# Layer3.net
KiCad netlist of a schematic drawn in EAGLE
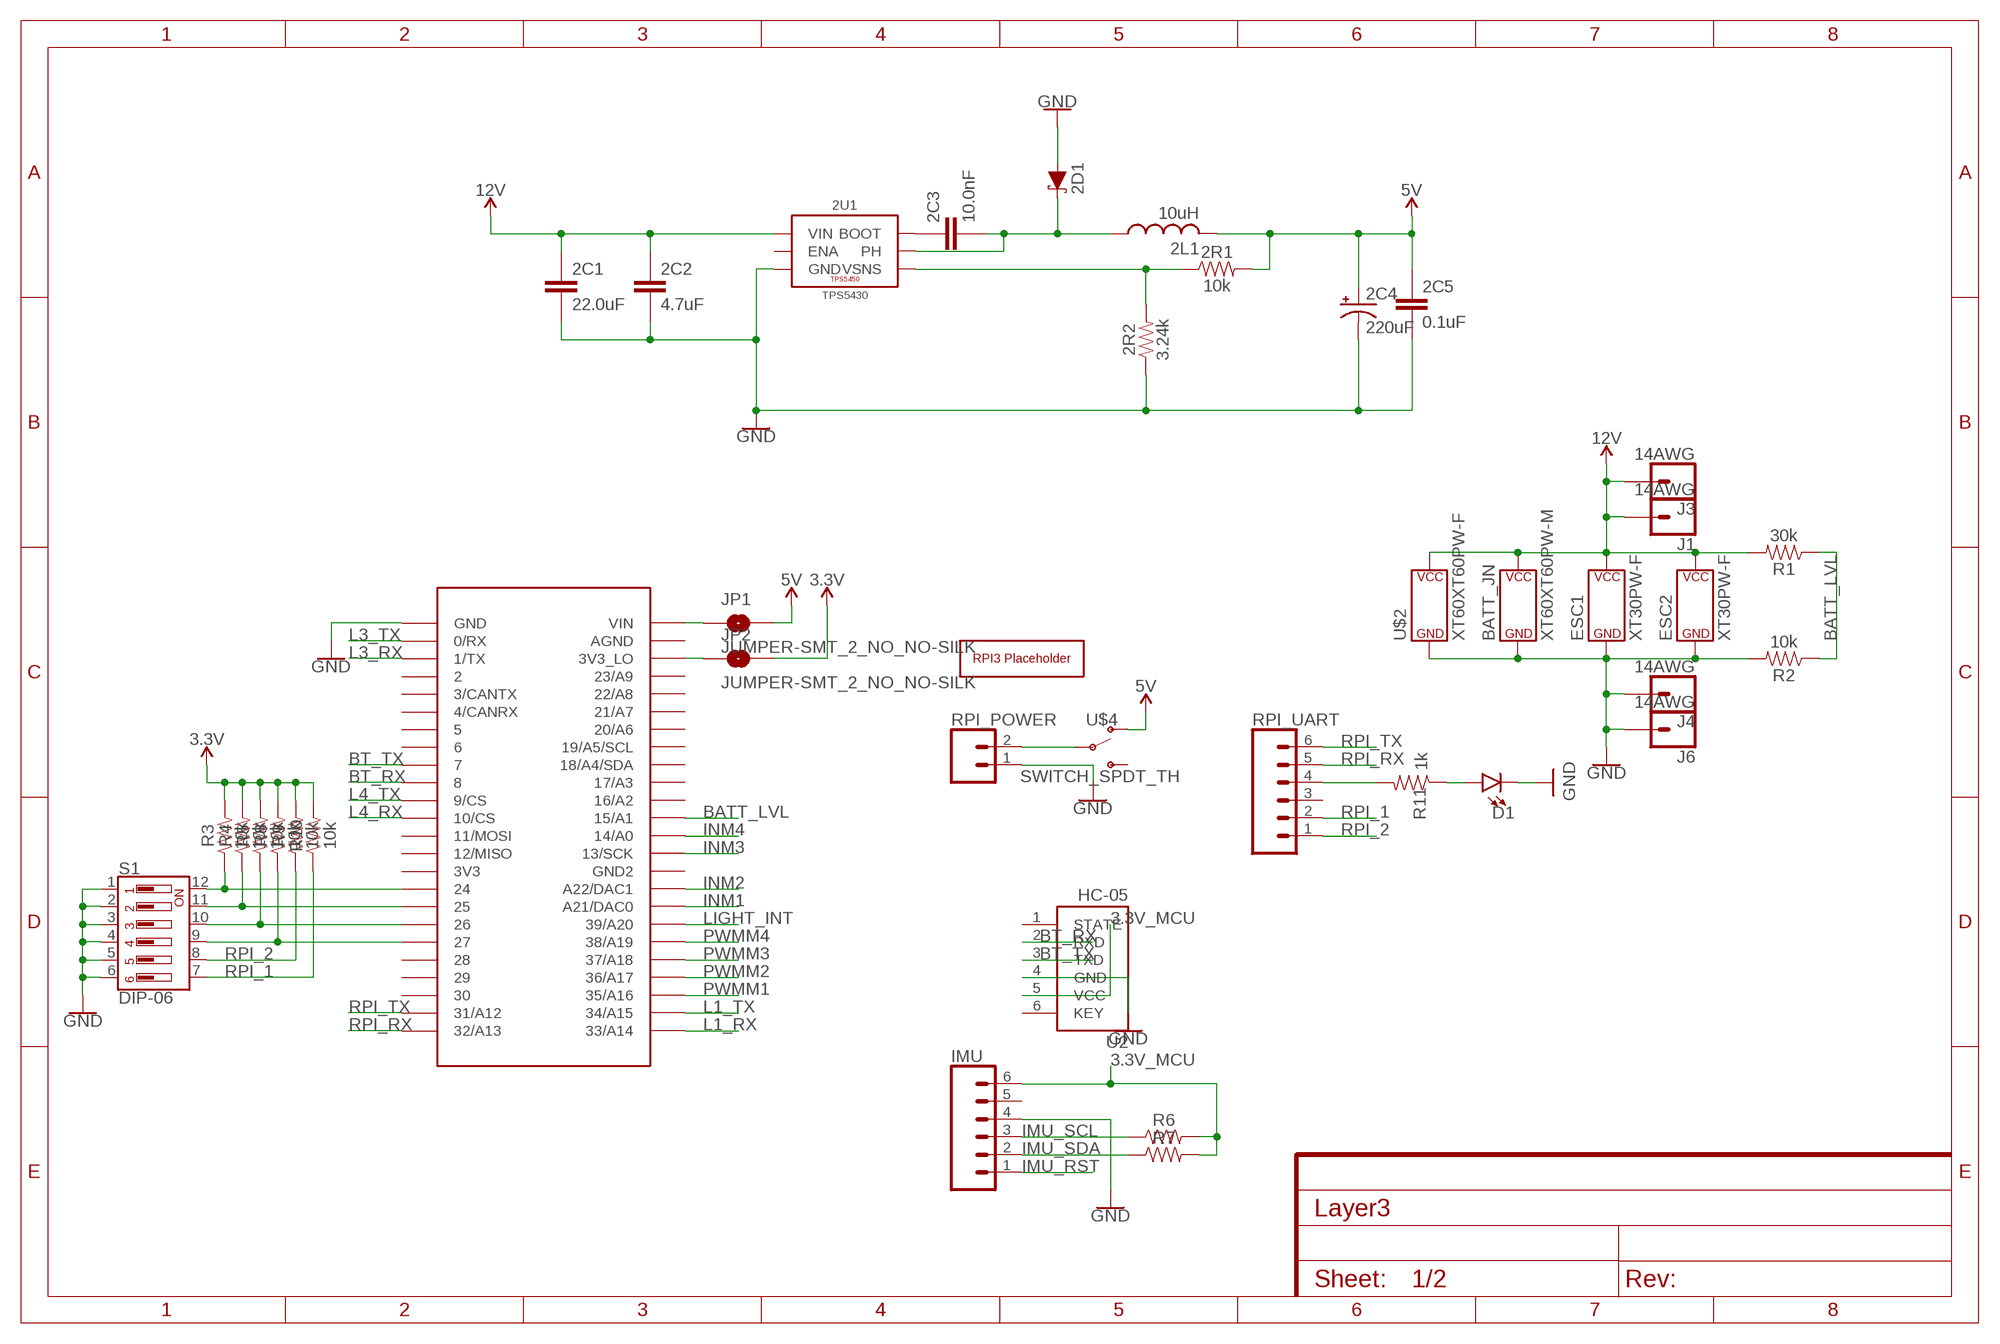
[diagram p0: schematic, sheet 1]
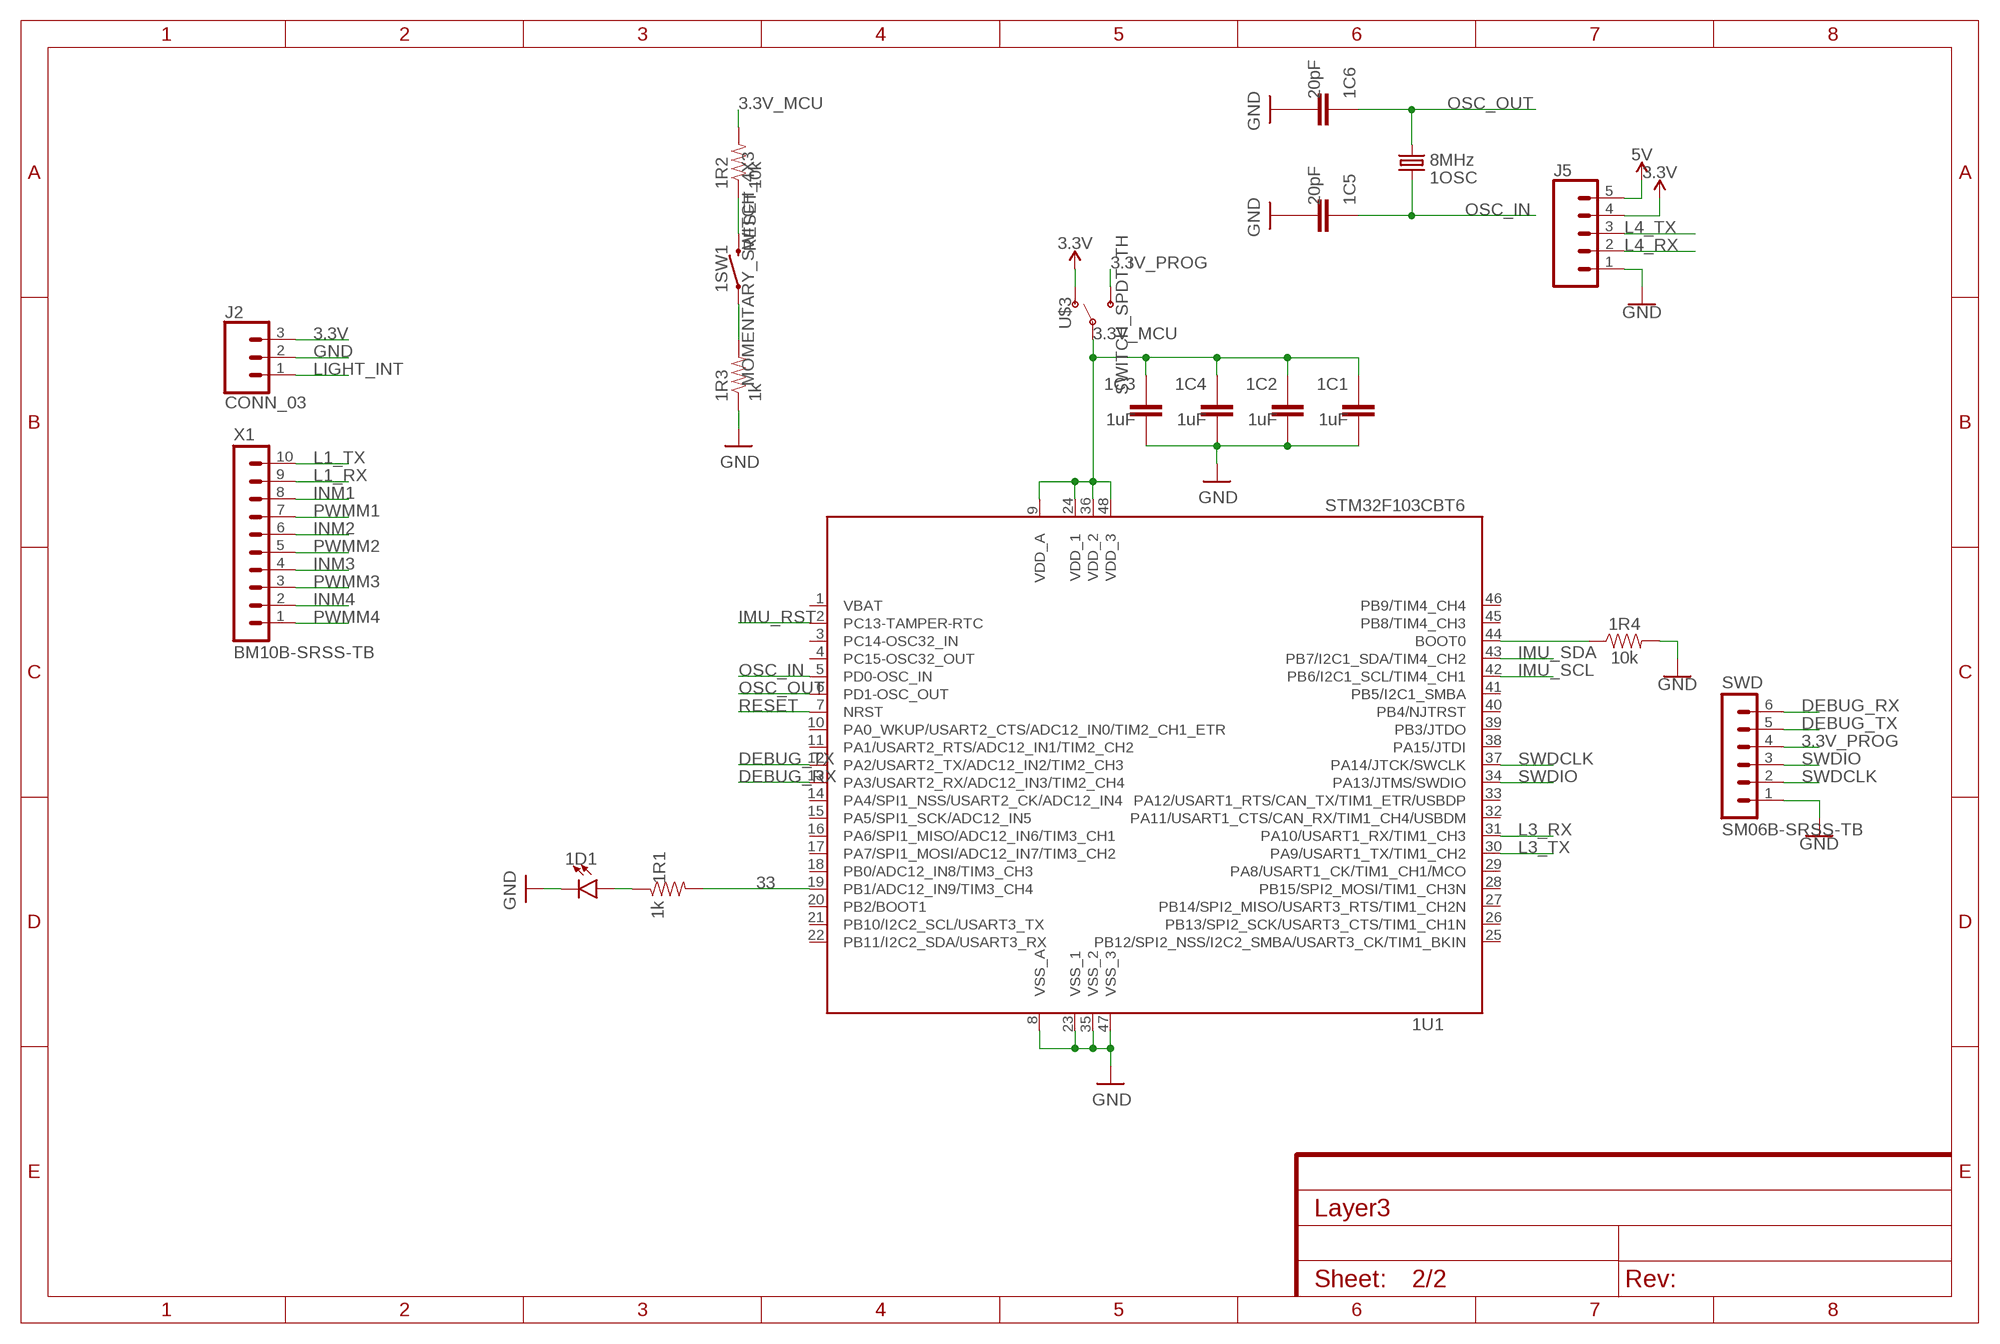
[diagram p1: schematic, sheet 2]

(export (version "E")
  (design (tool "Eeschema 10.0.6"))
  (components
    (comp (ref "1C1")
      (value "1uF")
      (footprint "eagle-import:C0603")
      (libsource (lib "eagle-import") (part "CAPACITOR0603"))
    )
    (comp (ref "1C2")
      (value "1uF")
      (footprint "eagle-import:C0603")
      (libsource (lib "eagle-import") (part "CAPACITOR0603"))
    )
    (comp (ref "1C3")
      (value "1uF")
      (footprint "eagle-import:C0603")
      (libsource (lib "eagle-import") (part "CAPACITOR0603"))
    )
    (comp (ref "1C4")
      (value "1uF")
      (footprint "eagle-import:C0603")
      (libsource (lib "eagle-import") (part "CAPACITOR0603"))
    )
    (comp (ref "1C5")
      (value "20pF")
      (footprint "eagle-import:C0603")
      (libsource (lib "eagle-import") (part "CAPACITOR0603"))
    )
    (comp (ref "1C6")
      (value "20pF")
      (footprint "eagle-import:C0603")
      (libsource (lib "eagle-import") (part "CAPACITOR0603"))
    )
    (comp (ref "1D1")
      (value "BLUE")
      (footprint "eagle-import:LED-0603")
      (libsource (lib "eagle-import") (part "LED0603"))
    )
    (comp (ref "1OSC")
      (value "8MHz")
      (footprint "eagle-import:CRYSTAL-SMD-5X3.2-2PAD")
      (libsource (lib "eagle-import") (part "CRYSTAL_5032"))
    )
    (comp (ref "1R1")
      (value "1k")
      (footprint "eagle-import:R0603")
      (libsource (lib "eagle-import") (part "RESISTOR0603"))
    )
    (comp (ref "1R2")
      (value "10k")
      (footprint "eagle-import:R0603")
      (libsource (lib "eagle-import") (part "RESISTOR0603"))
    )
    (comp (ref "1R3")
      (value "1k")
      (footprint "eagle-import:R0603")
      (libsource (lib "eagle-import") (part "RESISTOR0603"))
    )
    (comp (ref "1R4")
      (value "10k")
      (footprint "eagle-import:R0603")
      (libsource (lib "eagle-import") (part "RESISTOR0603"))
    )
    (comp (ref "1SW1")
      (value "MOMENTARY_SWITCH_4X3")
      (footprint "eagle-import:MOMENTARY_SWITCH_4X3")
      (libsource (lib "eagle-import") (part "MOMENTARY_SWITCH_4X3"))
    )
    (comp (ref "1U1")
      (value "STM32F103CBT6")
      (footprint "eagle-import:LQFP48")
      (libsource (lib "eagle-import") (part "STM32F103CBT6"))
    )
    (comp (ref "J2")
      (value "CONN_03")
      (footprint "eagle-import:1X03_LOCK")
      (libsource (lib "eagle-import") (part "CONN_03"))
    )
    (comp (ref "J5")
      (value "CONN_05LOCK")
      (footprint "eagle-import:1X05_LOCK")
      (libsource (lib "eagle-import") (part "CONN_05LOCK"))
    )
    (comp (ref "SWD")
      (value "SM06B-SRSS-TB")
      (footprint "eagle-import:SM06B-SRSS-TB")
      (libsource (lib "eagle-import") (part "SM06B-SRSS-TB"))
    )
    (comp (ref "U$3")
      (value "SWITCH_SPDT_TH")
      (footprint "eagle-import:SWITCH_SPDT_PTH_11.6X4.0MM_LOCK")
      (libsource (lib "eagle-import") (part "SWITCH_SPDT_TH"))
    )
    (comp (ref "X1")
      (value "BM10B-SRSS-TB")
      (footprint "eagle-import:BM10B-SRSS-TB")
      (libsource (lib "eagle-import") (part "BM10B-SRSS-TB"))
    )
    (comp (ref "2C1")
      (value "22.0uF")
      (footprint "eagle-import:C1210")
      (libsource (lib "eagle-import") (part "CAPACITOR1210"))
    )
    (comp (ref "2C2")
      (value "4.7uF")
      (footprint "eagle-import:C0603")
      (libsource (lib "eagle-import") (part "CAPACITOR0603"))
    )
    (comp (ref "2C3")
      (value "10.0nF")
      (footprint "eagle-import:C0603")
      (libsource (lib "eagle-import") (part "CAPACITOR0603"))
    )
    (comp (ref "2C4")
      (value "220uF")
      (footprint "eagle-import:D_7343-31R")
      (libsource (lib "eagle-import") (part "CPOL-USD/7343-31R"))
    )
    (comp (ref "2C5")
      (value "0.1uF")
      (footprint "eagle-import:C0603")
      (libsource (lib "eagle-import") (part "CAPACITOR0603"))
    )
    (comp (ref "2D1")
      (value "3A/40V/500mV")
      (footprint "eagle-import:SMA-DIODE")
      (libsource (lib "eagle-import") (part "DIODE-SCHOTTKY"))
    )
    (comp (ref "2L1")
      (value "10uH")
      (footprint "eagle-import:SWPA8040")
      (libsource (lib "eagle-import") (part "INDUCTORSWPA8040"))
    )
    (comp (ref "2R1")
      (value "10k")
      (footprint "eagle-import:R0603")
      (libsource (lib "eagle-import") (part "RESISTOR0603"))
    )
    (comp (ref "2R2")
      (value "3.24k")
      (footprint "eagle-import:R0603")
      (libsource (lib "eagle-import") (part "RESISTOR0603"))
    )
    (comp (ref "2U1")
      (value "TPS5430")
      (footprint "eagle-import:POWERPAD-SOIC-8")
      (libsource (lib "eagle-import") (part "TPS5450"))
    )
    (comp (ref "BATT_JN")
      (value "XT60XT60PW-M")
      (footprint "eagle-import:XT60PW-M")
      (libsource (lib "eagle-import") (part "XT60XT60PW-M"))
    )
    (comp (ref "D1")
      (value "BLUE")
      (footprint "eagle-import:LED-0603")
      (libsource (lib "eagle-import") (part "LED0603"))
    )
    (comp (ref "ESC1")
      (value "XT30PW-F")
      (footprint "eagle-import:XT30PW-F")
      (libsource (lib "eagle-import") (part "XT30PW-F"))
    )
    (comp (ref "ESC2")
      (value "XT30PW-F")
      (footprint "eagle-import:XT30PW-F")
      (libsource (lib "eagle-import") (part "XT30PW-F"))
    )
    (comp (ref "IMU")
      (value "CONN_06FEMALE_LOCK")
      (footprint "eagle-import:1X06_FEMALE_LOCK.010")
      (libsource (lib "eagle-import") (part "SparkFun-Connectors_513_CONN_06FEMALE_LOCK"))
    )
    (comp (ref "J1")
      (value "14AWG")
      (footprint "eagle-import:14AWG")
      (libsource (lib "eagle-import") (part "14AWG"))
    )
    (comp (ref "J3")
      (value "14AWG")
      (footprint "eagle-import:14AWG")
      (libsource (lib "eagle-import") (part "14AWG"))
    )
    (comp (ref "J4")
      (value "14AWG")
      (footprint "eagle-import:14AWG")
      (libsource (lib "eagle-import") (part "14AWG"))
    )
    (comp (ref "J6")
      (value "14AWG")
      (footprint "eagle-import:14AWG")
      (libsource (lib "eagle-import") (part "14AWG"))
    )
    (comp (ref "JP1")
      (value "JUMPER-SMT_2_NO_NO-SILK")
      (footprint "eagle-import:SMT-JUMPER_2_NO_NO-SILK")
      (libsource (lib "eagle-import") (part "JUMPER-SMT_2_NO_NO-SILK"))
    )
    (comp (ref "JP2")
      (value "JUMPER-SMT_2_NO_NO-SILK")
      (footprint "eagle-import:SMT-JUMPER_2_NO_NO-SILK")
      (libsource (lib "eagle-import") (part "JUMPER-SMT_2_NO_NO-SILK"))
    )
    (comp (ref "PCB1")
      (value "RPI3")
      (footprint "eagle-import:RPI3")
      (libsource (lib "eagle-import") (part "RPI3"))
    )
    (comp (ref "R1")
      (value "30k")
      (footprint "eagle-import:R0603")
      (libsource (lib "eagle-import") (part "RESISTOR0603"))
    )
    (comp (ref "R2")
      (value "10k")
      (footprint "eagle-import:R0603")
      (libsource (lib "eagle-import") (part "RESISTOR0603"))
    )
    (comp (ref "R3")
      (value "10k")
      (footprint "eagle-import:R0603")
      (libsource (lib "eagle-import") (part "RESISTOR0603"))
    )
    (comp (ref "R4")
      (value "10k")
      (footprint "eagle-import:R0603")
      (libsource (lib "eagle-import") (part "RESISTOR0603"))
    )
    (comp (ref "R5")
      (value "10k")
      (footprint "eagle-import:R0603")
      (libsource (lib "eagle-import") (part "RESISTOR0603"))
    )
    (comp (ref "R6")
      (value "RESISTOR0603")
      (footprint "eagle-import:R0603")
      (libsource (lib "eagle-import") (part "RESISTOR0603"))
    )
    (comp (ref "R7")
      (value "RESISTOR0603")
      (footprint "eagle-import:R0603")
      (libsource (lib "eagle-import") (part "RESISTOR0603"))
    )
    (comp (ref "R8")
      (value "10k")
      (footprint "eagle-import:R0603")
      (libsource (lib "eagle-import") (part "RESISTOR0603"))
    )
    (comp (ref "R9")
      (value "10k")
      (footprint "eagle-import:R0603")
      (libsource (lib "eagle-import") (part "RESISTOR0603"))
    )
    (comp (ref "R10")
      (value "10k")
      (footprint "eagle-import:R0603")
      (libsource (lib "eagle-import") (part "RESISTOR0603"))
    )
    (comp (ref "R11")
      (value "1k")
      (footprint "eagle-import:R0603")
      (libsource (lib "eagle-import") (part "RESISTOR0603"))
    )
    (comp (ref "RPI_POWER")
      (value "CONN_02LOCK")
      (footprint "eagle-import:1X02_LOCK")
      (libsource (lib "eagle-import") (part "CONN_02LOCK"))
    )
    (comp (ref "RPI_UART")
      (value "CONN_06LOCK")
      (footprint "eagle-import:1X06_LOCK")
      (libsource (lib "eagle-import") (part "CONN_06LOCK"))
    )
    (comp (ref "S1")
      (value "DIP-06")
      (footprint "eagle-import:DIPSWITCH-06-SMD")
      (libsource (lib "eagle-import") (part "DIP-06"))
    )
    (comp (ref "U$1")
      (value "TEENSY_3.5/3.6_NO_MIDDLE")
      (footprint "eagle-import:TEENSY_3.5_3.6_NO_MIDDLE")
      (libsource (lib "eagle-import") (part "TEENSY_3.5/3.6_NO_MIDDLE"))
    )
    (comp (ref "U$2")
      (value "XT60XT60PW-F")
      (footprint "eagle-import:XT60PW-F")
      (libsource (lib "eagle-import") (part "XT60XT60PW-F"))
    )
    (comp (ref "U$4")
      (value "SWITCH_SPDT_TH")
      (footprint "eagle-import:SWITCH_SPDT_PTH_11.6X4.0MM_LOCK")
      (libsource (lib "eagle-import") (part "SWITCH_SPDT_TH"))
    )
    (comp (ref "U2")
      (value "HC-05_BENT")
      (footprint "eagle-import:HC-05_BENT")
      (libsource (lib "eagle-import") (part "HC-05_BENT"))
    )
  )
  (nets
    (net (code "1") (name "3.3V") (class "Default")
      (node (ref "J2") (pin "3") (pinfunction "3_3") (pintype "passive"))
      (node (ref "J5") (pin "4") (pinfunction "4_4") (pintype "passive"))
      (node (ref "JP2") (pin "2") (pinfunction "2_2") (pintype "passive"))
      (node (ref "R10") (pin "2") (pinfunction "2_2") (pintype "passive"))
      (node (ref "R3") (pin "2") (pinfunction "2_2") (pintype "passive"))
      (node (ref "R4") (pin "2") (pinfunction "2_2") (pintype "passive"))
      (node (ref "R5") (pin "2") (pinfunction "2_2") (pintype "passive"))
      (node (ref "R8") (pin "2") (pinfunction "2_2") (pintype "passive"))
      (node (ref "R9") (pin "2") (pinfunction "2_2") (pintype "passive"))
      (node (ref "U$3") (pin "1") (pinfunction "O_1") (pintype "passive"))
    )
    (net (code "2") (name "3.3V_MCU") (class "Default")
      (node (ref "1C1") (pin "1") (pinfunction "1_1") (pintype "passive"))
      (node (ref "1C2") (pin "1") (pinfunction "1_1") (pintype "passive"))
      (node (ref "1C3") (pin "1") (pinfunction "1_1") (pintype "passive"))
      (node (ref "1C4") (pin "1") (pinfunction "1_1") (pintype "passive"))
      (node (ref "1R2") (pin "2") (pinfunction "2_2") (pintype "passive"))
      (node (ref "1U1") (pin "24") (pinfunction "VDD_1_24") (pintype "power_in"))
      (node (ref "1U1") (pin "36") (pinfunction "VDD_2_36") (pintype "power_in"))
      (node (ref "1U1") (pin "48") (pinfunction "VDD_3_48") (pintype "power_in"))
      (node (ref "1U1") (pin "9") (pinfunction "VDD_A_9") (pintype "power_in"))
      (node (ref "IMU") (pin "6") (pinfunction "6_6") (pintype "passive"))
      (node (ref "R6") (pin "2") (pinfunction "2_2") (pintype "passive"))
      (node (ref "R7") (pin "2") (pinfunction "2_2") (pintype "passive"))
      (node (ref "U$3") (pin "2") (pinfunction "P_2") (pintype "passive"))
      (node (ref "U2") (pin "5") (pinfunction "VCC_5") (pintype "power_in"))
    )
    (net (code "3") (name "3.3V_PROG") (class "Default")
      (node (ref "SWD") (pin "4") (pinfunction "4_4") (pintype "passive"))
      (node (ref "U$3") (pin "3") (pinfunction "S_3") (pintype "passive"))
    )
    (net (code "4") (name "5V") (class "Default")
      (node (ref "2C4") (pin "+") (pinfunction "+_+") (pintype "passive"))
      (node (ref "2C5") (pin "1") (pinfunction "1_1") (pintype "passive"))
      (node (ref "2L1") (pin "P2") (pinfunction "2_P2") (pintype "passive"))
      (node (ref "2R1") (pin "2") (pinfunction "2_2") (pintype "passive"))
      (node (ref "J5") (pin "5") (pinfunction "5_5") (pintype "passive"))
      (node (ref "JP1") (pin "2") (pinfunction "2_2") (pintype "passive"))
      (node (ref "U$4") (pin "1") (pinfunction "O_1") (pintype "passive"))
    )
    (net (code "5") (name "12V") (class "Default")
      (node (ref "2C1") (pin "1") (pinfunction "1_1") (pintype "passive"))
      (node (ref "2C2") (pin "1") (pinfunction "1_1") (pintype "passive"))
      (node (ref "2U1") (pin "7") (pinfunction "VIN_7") (pintype "power_in"))
      (node (ref "BATT_JN") (pin "+") (pinfunction "P$V+_+") (pintype "bidirectional"))
      (node (ref "ESC1") (pin "+") (pinfunction "P$V+_+") (pintype "bidirectional"))
      (node (ref "ESC2") (pin "+") (pinfunction "P$V+_+") (pintype "bidirectional"))
      (node (ref "J1") (pin "P$1") (pinfunction "1_P$1") (pintype "passive"))
      (node (ref "J3") (pin "P$1") (pinfunction "1_P$1") (pintype "passive"))
      (node (ref "R1") (pin "2") (pinfunction "2_2") (pintype "passive"))
      (node (ref "U$2") (pin "+") (pinfunction "P$V+_+") (pintype "bidirectional"))
    )
    (net (code "6") (name "33") (class "Default")
      (node (ref "1R1") (pin "2") (pinfunction "2_2") (pintype "passive"))
      (node (ref "1U1") (pin "19") (pinfunction "PB1/ADC12_IN9/TIM3_CH4_19") (pintype "bidirectional"))
    )
    (net (code "7") (name "BATT_LVL") (class "Default")
      (node (ref "R1") (pin "1") (pinfunction "1_1") (pintype "passive"))
      (node (ref "R2") (pin "1") (pinfunction "1_1") (pintype "passive"))
      (node (ref "U$1") (pin "15/A1") (pinfunction "15/A1_15/A1") (pintype "bidirectional"))
    )
    (net (code "8") (name "BT_RX") (class "Default")
      (node (ref "U$1") (pin "8") (pinfunction "8_8") (pintype "bidirectional"))
      (node (ref "U2") (pin "2") (pinfunction "RXD_2") (pintype "bidirectional"))
    )
    (net (code "9") (name "BT_TX") (class "Default")
      (node (ref "U$1") (pin "7") (pinfunction "7_7") (pintype "bidirectional"))
      (node (ref "U2") (pin "3") (pinfunction "TXD_3") (pintype "bidirectional"))
    )
    (net (code "10") (name "DEBUG_RX") (class "Default")
      (node (ref "1U1") (pin "13") (pinfunction "PA3/USART2_RX/ADC12_IN3/TIM2_CH4_13") (pintype "bidirectional"))
      (node (ref "SWD") (pin "6") (pinfunction "6_6") (pintype "passive"))
    )
    (net (code "11") (name "DEBUG_TX") (class "Default")
      (node (ref "1U1") (pin "12") (pinfunction "PA2/USART2_TX/ADC12_IN2/TIM2_CH3_12") (pintype "bidirectional"))
      (node (ref "SWD") (pin "5") (pinfunction "5_5") (pintype "passive"))
    )
    (net (code "12") (name "GND") (class "Default")
      (node (ref "1C1") (pin "2") (pinfunction "2_2") (pintype "passive"))
      (node (ref "1C2") (pin "2") (pinfunction "2_2") (pintype "passive"))
      (node (ref "1C3") (pin "2") (pinfunction "2_2") (pintype "passive"))
      (node (ref "1C4") (pin "2") (pinfunction "2_2") (pintype "passive"))
      (node (ref "1C5") (pin "2") (pinfunction "2_2") (pintype "passive"))
      (node (ref "1C6") (pin "2") (pinfunction "2_2") (pintype "passive"))
      (node (ref "1D1") (pin "C") (pinfunction "C_C") (pintype "passive"))
      (node (ref "1R3") (pin "1") (pinfunction "1_1") (pintype "passive"))
      (node (ref "1R4") (pin "2") (pinfunction "2_2") (pintype "passive"))
      (node (ref "1U1") (pin "23") (pinfunction "VSS_1_23") (pintype "power_in"))
      (node (ref "1U1") (pin "35") (pinfunction "VSS_2_35") (pintype "power_in"))
      (node (ref "1U1") (pin "47") (pinfunction "VSS_3_47") (pintype "power_in"))
      (node (ref "1U1") (pin "8") (pinfunction "VSS_A_8") (pintype "power_in"))
      (node (ref "2C1") (pin "2") (pinfunction "2_2") (pintype "passive"))
      (node (ref "2C2") (pin "2") (pinfunction "2_2") (pintype "passive"))
      (node (ref "2C4") (pin "-") (pinfunction "-_-") (pintype "passive"))
      (node (ref "2C5") (pin "2") (pinfunction "2_2") (pintype "passive"))
      (node (ref "2D1") (pin "A") (pinfunction "A_A") (pintype "passive"))
      (node (ref "2R2") (pin "1") (pinfunction "1_1") (pintype "passive"))
      (node (ref "2U1") (pin "6") (pinfunction "GND_6") (pintype "power_in"))
      (node (ref "2U1") (pin "9") (pinfunction "GND_9") (pintype "power_in"))
      (node (ref "2U1") (pin "P$1") (pinfunction "GND_P$1") (pintype "power_in"))
      (node (ref "2U1") (pin "P$2") (pinfunction "GND_P$2") (pintype "power_in"))
      (node (ref "2U1") (pin "P$3") (pinfunction "GND_P$3") (pintype "power_in"))
      (node (ref "2U1") (pin "P$4") (pinfunction "GND_P$4") (pintype "power_in"))
      (node (ref "2U1") (pin "P$5") (pinfunction "GND_P$5") (pintype "power_in"))
      (node (ref "2U1") (pin "P$6") (pinfunction "GND_P$6") (pintype "power_in"))
      (node (ref "BATT_JN") (pin "-") (pinfunction "P$V-_-") (pintype "bidirectional"))
      (node (ref "D1") (pin "C") (pinfunction "C_C") (pintype "passive"))
      (node (ref "ESC1") (pin "-") (pinfunction "P$V-_-") (pintype "bidirectional"))
      (node (ref "ESC2") (pin "-") (pinfunction "P$V-_-") (pintype "bidirectional"))
      (node (ref "IMU") (pin "4") (pinfunction "4_4") (pintype "passive"))
      (node (ref "J2") (pin "2") (pinfunction "2_2") (pintype "passive"))
      (node (ref "J4") (pin "P$1") (pinfunction "1_P$1") (pintype "passive"))
      (node (ref "J5") (pin "1") (pinfunction "1_1") (pintype "passive"))
      (node (ref "J6") (pin "P$1") (pinfunction "1_P$1") (pintype "passive"))
      (node (ref "R2") (pin "2") (pinfunction "2_2") (pintype "passive"))
      (node (ref "RPI_POWER") (pin "1") (pinfunction "1_1") (pintype "passive"))
      (node (ref "S1") (pin "1") (pinfunction "1_1") (pintype "bidirectional"))
      (node (ref "S1") (pin "2") (pinfunction "2_2") (pintype "bidirectional"))
      (node (ref "S1") (pin "3") (pinfunction "3_3") (pintype "bidirectional"))
      (node (ref "S1") (pin "4") (pinfunction "4_4") (pintype "bidirectional"))
      (node (ref "S1") (pin "5") (pinfunction "5_5") (pintype "bidirectional"))
      (node (ref "S1") (pin "6") (pinfunction "6_6") (pintype "bidirectional"))
      (node (ref "SWD") (pin "1") (pinfunction "1_1") (pintype "passive"))
      (node (ref "U$1") (pin "GND") (pinfunction "GND_GND") (pintype "bidirectional"))
      (node (ref "U$2") (pin "-") (pinfunction "P$V-_-") (pintype "bidirectional"))
      (node (ref "U2") (pin "4") (pinfunction "GND_4") (pintype "power_in"))
    )
    (net (code "13") (name "IMU_RST") (class "Default")
      (node (ref "1U1") (pin "2") (pinfunction "PC13-TAMPER-RTC_2") (pintype "input"))
      (node (ref "IMU") (pin "1") (pinfunction "1_1") (pintype "passive"))
    )
    (net (code "14") (name "IMU_SCL") (class "Default")
      (node (ref "1U1") (pin "42") (pinfunction "PB6/I2C1_SCL/TIM4_CH1_42") (pintype "input"))
      (node (ref "IMU") (pin "3") (pinfunction "3_3") (pintype "passive"))
      (node (ref "R6") (pin "1") (pinfunction "1_1") (pintype "passive"))
    )
    (net (code "15") (name "IMU_SDA") (class "Default")
      (node (ref "1U1") (pin "43") (pinfunction "PB7/I2C1_SDA/TIM4_CH2_43") (pintype "bidirectional"))
      (node (ref "IMU") (pin "2") (pinfunction "2_2") (pintype "passive"))
      (node (ref "R7") (pin "1") (pinfunction "1_1") (pintype "passive"))
    )
    (net (code "16") (name "INM1") (class "Default")
      (node (ref "U$1") (pin "A21/DAC0") (pinfunction "A21/DAC0_A21/DAC0") (pintype "bidirectional"))
      (node (ref "X1") (pin "8") (pinfunction "8_8") (pintype "passive"))
    )
    (net (code "17") (name "INM2") (class "Default")
      (node (ref "U$1") (pin "A22/DAC1") (pinfunction "A22/DAC1_A22/DAC1") (pintype "bidirectional"))
      (node (ref "X1") (pin "6") (pinfunction "6_6") (pintype "passive"))
    )
    (net (code "18") (name "INM3") (class "Default")
      (node (ref "U$1") (pin "13/SCK") (pinfunction "13/SCK_13/SCK") (pintype "bidirectional"))
      (node (ref "X1") (pin "4") (pinfunction "4_4") (pintype "passive"))
    )
    (net (code "19") (name "INM4") (class "Default")
      (node (ref "U$1") (pin "14/A0") (pinfunction "14/A0_14/A0") (pintype "bidirectional"))
      (node (ref "X1") (pin "2") (pinfunction "2_2") (pintype "passive"))
    )
    (net (code "20") (name "L1_RX") (class "Default")
      (node (ref "U$1") (pin "33/A14") (pinfunction "33/A14_33/A14") (pintype "bidirectional"))
      (node (ref "X1") (pin "9") (pinfunction "9_9") (pintype "passive"))
    )
    (net (code "21") (name "L1_TX") (class "Default")
      (node (ref "U$1") (pin "34/A15") (pinfunction "34/A15_34/A15") (pintype "bidirectional"))
      (node (ref "X1") (pin "10") (pinfunction "10_10") (pintype "passive"))
    )
    (net (code "22") (name "L3_RX") (class "Default")
      (node (ref "1U1") (pin "31") (pinfunction "PA10/USART1_RX/TIM1_CH3_31") (pintype "bidirectional"))
      (node (ref "U$1") (pin "1/TX") (pinfunction "1/TX_1/TX") (pintype "bidirectional"))
    )
    (net (code "23") (name "L3_TX") (class "Default")
      (node (ref "1U1") (pin "30") (pinfunction "PA9/USART1_TX/TIM1_CH2_30") (pintype "input"))
      (node (ref "U$1") (pin "0/RX") (pinfunction "0/RX_0/RX") (pintype "bidirectional"))
    )
    (net (code "24") (name "L4_RX") (class "Default")
      (node (ref "J5") (pin "2") (pinfunction "2_2") (pintype "passive"))
      (node (ref "U$1") (pin "10/CS") (pinfunction "10/CS_10/CS") (pintype "bidirectional"))
    )
    (net (code "25") (name "L4_TX") (class "Default")
      (node (ref "J5") (pin "3") (pinfunction "3_3") (pintype "passive"))
      (node (ref "U$1") (pin "9/CS") (pinfunction "9/CS_9/CS") (pintype "bidirectional"))
    )
    (net (code "26") (name "LIGHT_INT") (class "Default")
      (node (ref "J2") (pin "1") (pinfunction "1_1") (pintype "passive"))
      (node (ref "U$1") (pin "39/A20") (pinfunction "39/A20_39/A20") (pintype "bidirectional"))
    )
    (net (code "27") (name "Net-(1D1-PadA)") (class "Default")
      (node (ref "1D1") (pin "A") (pinfunction "A_A") (pintype "passive"))
      (node (ref "1R1") (pin "1") (pinfunction "1_1") (pintype "passive"))
    )
    (net (code "28") (name "Net-(1SW1-1)") (class "Default")
      (node (ref "1R3") (pin "2") (pinfunction "2_2") (pintype "passive"))
      (node (ref "1SW1") (pin "P$1") (pinfunction "1_P$1") (pintype "passive"))
    )
    (net (code "29") (name "Net-(1U1-BOOT0)") (class "Default")
      (node (ref "1R4") (pin "1") (pinfunction "1_1") (pintype "passive"))
      (node (ref "1U1") (pin "44") (pinfunction "BOOT0_44") (pintype "input"))
    )
    (net (code "30") (name "Net-(2L1-1)") (class "Default")
      (node (ref "2C3") (pin "2") (pinfunction "2_2") (pintype "passive"))
      (node (ref "2D1") (pin "C") (pinfunction "C_C") (pintype "passive"))
      (node (ref "2L1") (pin "P1") (pinfunction "1_P1") (pintype "passive"))
      (node (ref "2U1") (pin "8") (pinfunction "PH_8") (pintype "bidirectional"))
    )
    (net (code "31") (name "Net-(2U1-BOOT)") (class "Default")
      (node (ref "2C3") (pin "1") (pinfunction "1_1") (pintype "passive"))
      (node (ref "2U1") (pin "1") (pinfunction "BOOT_1") (pintype "bidirectional"))
    )
    (net (code "32") (name "Net-(2U1-VSNS)") (class "Default")
      (node (ref "2R1") (pin "1") (pinfunction "1_1") (pintype "passive"))
      (node (ref "2R2") (pin "2") (pinfunction "2_2") (pintype "passive"))
      (node (ref "2U1") (pin "4") (pinfunction "VSNS_4") (pintype "input"))
    )
    (net (code "33") (name "Net-(D1-PadA)") (class "Default")
      (node (ref "D1") (pin "A") (pinfunction "A_A") (pintype "passive"))
      (node (ref "R11") (pin "1") (pinfunction "1_1") (pintype "passive"))
    )
    (net (code "34") (name "Net-(JP1-Pad1)") (class "Default")
      (node (ref "JP1") (pin "1") (pinfunction "1_1") (pintype "passive"))
      (node (ref "U$1") (pin "VIN") (pinfunction "VIN_VIN") (pintype "bidirectional"))
    )
    (net (code "35") (name "Net-(JP2-Pad1)") (class "Default")
      (node (ref "JP2") (pin "1") (pinfunction "1_1") (pintype "passive"))
      (node (ref "U$1") (pin "3V3_LO") (pinfunction "3V3_LO_3V3_LO") (pintype "bidirectional"))
    )
    (net (code "36") (name "Net-(R3-Pad1)") (class "Default")
      (node (ref "R3") (pin "1") (pinfunction "1_1") (pintype "passive"))
      (node (ref "S1") (pin "12") (pinfunction "12_12") (pintype "bidirectional"))
      (node (ref "U$1") (pin "24") (pinfunction "24_24") (pintype "bidirectional"))
    )
    (net (code "37") (name "Net-(R4-Pad1)") (class "Default")
      (node (ref "R4") (pin "1") (pinfunction "1_1") (pintype "passive"))
      (node (ref "S1") (pin "11") (pinfunction "11_11") (pintype "bidirectional"))
      (node (ref "U$1") (pin "25") (pinfunction "25_25") (pintype "bidirectional"))
    )
    (net (code "38") (name "Net-(R5-Pad1)") (class "Default")
      (node (ref "R5") (pin "1") (pinfunction "1_1") (pintype "passive"))
      (node (ref "S1") (pin "10") (pinfunction "10_10") (pintype "bidirectional"))
      (node (ref "U$1") (pin "26") (pinfunction "26_26") (pintype "bidirectional"))
    )
    (net (code "39") (name "Net-(R8-Pad1)") (class "Default")
      (node (ref "R8") (pin "1") (pinfunction "1_1") (pintype "passive"))
      (node (ref "S1") (pin "9") (pinfunction "9_9") (pintype "bidirectional"))
      (node (ref "U$1") (pin "27") (pinfunction "27_27") (pintype "bidirectional"))
    )
    (net (code "40") (name "Net-(R11-Pad2)") (class "Default")
      (node (ref "R11") (pin "2") (pinfunction "2_2") (pintype "passive"))
      (node (ref "RPI_UART") (pin "4") (pinfunction "4_4") (pintype "passive"))
    )
    (net (code "41") (name "Net-(U$4-P)") (class "Default")
      (node (ref "RPI_POWER") (pin "2") (pinfunction "2_2") (pintype "passive"))
      (node (ref "U$4") (pin "2") (pinfunction "P_2") (pintype "passive"))
    )
    (net (code "42") (name "OSC_IN") (class "Default")
      (node (ref "1C5") (pin "1") (pinfunction "1_1") (pintype "passive"))
      (node (ref "1OSC") (pin "P$2") (pinfunction "2_P$2") (pintype "passive"))
      (node (ref "1U1") (pin "5") (pinfunction "PD0-OSC_IN_5") (pintype "input"))
    )
    (net (code "43") (name "OSC_OUT") (class "Default")
      (node (ref "1C6") (pin "1") (pinfunction "1_1") (pintype "passive"))
      (node (ref "1OSC") (pin "P$1") (pinfunction "1_P$1") (pintype "passive"))
      (node (ref "1U1") (pin "6") (pinfunction "PD1-OSC_OUT_6") (pintype "input"))
    )
    (net (code "44") (name "PWMM1") (class "Default")
      (node (ref "U$1") (pin "35/A16") (pinfunction "35/A16_35/A16") (pintype "bidirectional"))
      (node (ref "X1") (pin "7") (pinfunction "7_7") (pintype "passive"))
    )
    (net (code "45") (name "PWMM2") (class "Default")
      (node (ref "U$1") (pin "36/A17") (pinfunction "36/A17_36/A17") (pintype "bidirectional"))
      (node (ref "X1") (pin "5") (pinfunction "5_5") (pintype "passive"))
    )
    (net (code "46") (name "PWMM3") (class "Default")
      (node (ref "U$1") (pin "37/A18") (pinfunction "37/A18_37/A18") (pintype "bidirectional"))
      (node (ref "X1") (pin "3") (pinfunction "3_3") (pintype "passive"))
    )
    (net (code "47") (name "PWMM4") (class "Default")
      (node (ref "U$1") (pin "38/A19") (pinfunction "38/A19_38/A19") (pintype "bidirectional"))
      (node (ref "X1") (pin "1") (pinfunction "1_1") (pintype "passive"))
    )
    (net (code "48") (name "RESET") (class "Default")
      (node (ref "1R2") (pin "1") (pinfunction "1_1") (pintype "passive"))
      (node (ref "1SW1") (pin "P$2") (pinfunction "2_P$2") (pintype "passive"))
      (node (ref "1U1") (pin "7") (pinfunction "NRST_7") (pintype "input"))
    )
    (net (code "49") (name "RPI_1") (class "Default")
      (node (ref "R10") (pin "1") (pinfunction "1_1") (pintype "passive"))
      (node (ref "RPI_UART") (pin "2") (pinfunction "2_2") (pintype "passive"))
      (node (ref "S1") (pin "7") (pinfunction "7_7") (pintype "bidirectional"))
    )
    (net (code "50") (name "RPI_2") (class "Default")
      (node (ref "R9") (pin "1") (pinfunction "1_1") (pintype "passive"))
      (node (ref "RPI_UART") (pin "1") (pinfunction "1_1") (pintype "passive"))
      (node (ref "S1") (pin "8") (pinfunction "8_8") (pintype "bidirectional"))
    )
    (net (code "51") (name "RPI_RX") (class "Default")
      (node (ref "RPI_UART") (pin "5") (pinfunction "5_5") (pintype "passive"))
      (node (ref "U$1") (pin "32/A13") (pinfunction "32/A13_32/A13") (pintype "bidirectional"))
    )
    (net (code "52") (name "RPI_TX") (class "Default")
      (node (ref "RPI_UART") (pin "6") (pinfunction "6_6") (pintype "passive"))
      (node (ref "U$1") (pin "31/A12") (pinfunction "31/A12_31/A12") (pintype "bidirectional"))
    )
    (net (code "53") (name "SWDCLK") (class "Default")
      (node (ref "1U1") (pin "37") (pinfunction "PA14/JTCK/SWCLK_37") (pintype "bidirectional"))
      (node (ref "SWD") (pin "2") (pinfunction "2_2") (pintype "passive"))
    )
    (net (code "54") (name "SWDIO") (class "Default")
      (node (ref "1U1") (pin "34") (pinfunction "PA13/JTMS/SWDIO_34") (pintype "bidirectional"))
      (node (ref "SWD") (pin "3") (pinfunction "3_3") (pintype "passive"))
    )
    (net (code "55") (name "VBAT") (class "Default")
      (node (ref "1U1") (pin "1") (pinfunction "VBAT_1") (pintype "power_in"))
    )
    (net (code "56") (name "unconnected-(1U1-PA0_WKUP{slash}USART2_CTS{slash}ADC12_IN0{slash}TIM2_CH1_ETR-Pad10)") (class "Default")
      (node (ref "1U1") (pin "10") (pinfunction "PA0_WKUP/USART2_CTS/ADC12_IN0/TIM2_CH1_ETR_10") (pintype "bidirectional"))
    )
    (net (code "57") (name "unconnected-(1U1-PA1{slash}USART2_RTS{slash}ADC12_IN1{slash}TIM2_CH2-Pad11)") (class "Default")
      (node (ref "1U1") (pin "11") (pinfunction "PA1/USART2_RTS/ADC12_IN1/TIM2_CH2_11") (pintype "bidirectional"))
    )
    (net (code "58") (name "unconnected-(1U1-PA4{slash}SPI1_NSS{slash}USART2_CK{slash}ADC12_IN4-Pad14)") (class "Default")
      (node (ref "1U1") (pin "14") (pinfunction "PA4/SPI1_NSS/USART2_CK/ADC12_IN4_14") (pintype "bidirectional"))
    )
    (net (code "59") (name "unconnected-(1U1-PA5{slash}SPI1_SCK{slash}ADC12_IN5-Pad15)") (class "Default")
      (node (ref "1U1") (pin "15") (pinfunction "PA5/SPI1_SCK/ADC12_IN5_15") (pintype "bidirectional"))
    )
    (net (code "60") (name "unconnected-(1U1-PA6{slash}SPI1_MISO{slash}ADC12_IN6{slash}TIM3_CH1-Pad16)") (class "Default")
      (node (ref "1U1") (pin "16") (pinfunction "PA6/SPI1_MISO/ADC12_IN6/TIM3_CH1_16") (pintype "bidirectional"))
    )
    (net (code "61") (name "unconnected-(1U1-PA7{slash}SPI1_MOSI{slash}ADC12_IN7{slash}TIM3_CH2-Pad17)") (class "Default")
      (node (ref "1U1") (pin "17") (pinfunction "PA7/SPI1_MOSI/ADC12_IN7/TIM3_CH2_17") (pintype "bidirectional"))
    )
    (net (code "62") (name "unconnected-(1U1-PA8{slash}USART1_CK{slash}TIM1_CH1{slash}MCO-Pad29)") (class "Default")
      (node (ref "1U1") (pin "29") (pinfunction "PA8/USART1_CK/TIM1_CH1/MCO_29") (pintype "bidirectional"))
    )
    (net (code "63") (name "unconnected-(1U1-PA11{slash}USART1_CTS{slash}CAN_RX{slash}TIM1_CH4{slash}USBDM-Pad32)") (class "Default")
      (node (ref "1U1") (pin "32") (pinfunction "PA11/USART1_CTS/CAN_RX/TIM1_CH4/USBDM_32") (pintype "bidirectional"))
    )
    (net (code "64") (name "unconnected-(1U1-PA12{slash}USART1_RTS{slash}CAN_TX{slash}TIM1_ETR{slash}USBDP-Pad33)") (class "Default")
      (node (ref "1U1") (pin "33") (pinfunction "PA12/USART1_RTS/CAN_TX/TIM1_ETR/USBDP_33") (pintype "bidirectional"))
    )
    (net (code "65") (name "unconnected-(1U1-PA15{slash}JTDI-Pad38)") (class "Default")
      (node (ref "1U1") (pin "38") (pinfunction "PA15/JTDI_38") (pintype "bidirectional"))
    )
    (net (code "66") (name "unconnected-(1U1-PB0{slash}ADC12_IN8{slash}TIM3_CH3-Pad18)") (class "Default")
      (node (ref "1U1") (pin "18") (pinfunction "PB0/ADC12_IN8/TIM3_CH3_18") (pintype "bidirectional"))
    )
    (net (code "67") (name "unconnected-(1U1-PB2{slash}BOOT1-Pad20)") (class "Default")
      (node (ref "1U1") (pin "20") (pinfunction "PB2/BOOT1_20") (pintype "bidirectional"))
    )
    (net (code "68") (name "unconnected-(1U1-PB3{slash}JTDO-Pad39)") (class "Default")
      (node (ref "1U1") (pin "39") (pinfunction "PB3/JTDO_39") (pintype "bidirectional"))
    )
    (net (code "69") (name "unconnected-(1U1-PB4{slash}NJTRST-Pad40)") (class "Default")
      (node (ref "1U1") (pin "40") (pinfunction "PB4/NJTRST_40") (pintype "bidirectional"))
    )
    (net (code "70") (name "unconnected-(1U1-PB5{slash}I2C1_SMBA-Pad41)") (class "Default")
      (node (ref "1U1") (pin "41") (pinfunction "PB5/I2C1_SMBA_41") (pintype "input"))
    )
    (net (code "71") (name "unconnected-(1U1-PB8{slash}TIM4_CH3-Pad45)") (class "Default")
      (node (ref "1U1") (pin "45") (pinfunction "PB8/TIM4_CH3_45") (pintype "bidirectional"))
    )
    (net (code "72") (name "unconnected-(1U1-PB9{slash}TIM4_CH4-Pad46)") (class "Default")
      (node (ref "1U1") (pin "46") (pinfunction "PB9/TIM4_CH4_46") (pintype "input"))
    )
    (net (code "73") (name "unconnected-(1U1-PB10{slash}I2C2_SCL{slash}USART3_TX-Pad21)") (class "Default")
      (node (ref "1U1") (pin "21") (pinfunction "PB10/I2C2_SCL/USART3_TX_21") (pintype "input"))
    )
    (net (code "74") (name "unconnected-(1U1-PB11{slash}I2C2_SDA{slash}USART3_RX-Pad22)") (class "Default")
      (node (ref "1U1") (pin "22") (pinfunction "PB11/I2C2_SDA/USART3_RX_22") (pintype "input"))
    )
    (net (code "75") (name "unconnected-(1U1-PB12{slash}SPI2_NSS{slash}I2C2_SMBA{slash}USART3_CK{slash}TIM1_BKIN-Pad25)") (class "Default")
      (node (ref "1U1") (pin "25") (pinfunction "PB12/SPI2_NSS/I2C2_SMBA/USART3_CK/TIM1_BKIN_25") (pintype "input"))
    )
    (net (code "76") (name "unconnected-(1U1-PB13{slash}SPI2_SCK{slash}USART3_CTS{slash}TIM1_CH1N-Pad26)") (class "Default")
      (node (ref "1U1") (pin "26") (pinfunction "PB13/SPI2_SCK/USART3_CTS/TIM1_CH1N_26") (pintype "input"))
    )
    (net (code "77") (name "unconnected-(1U1-PB14{slash}SPI2_MISO{slash}USART3_RTS{slash}TIM1_CH2N-Pad27)") (class "Default")
      (node (ref "1U1") (pin "27") (pinfunction "PB14/SPI2_MISO/USART3_RTS/TIM1_CH2N_27") (pintype "input"))
    )
    (net (code "78") (name "unconnected-(1U1-PB15{slash}SPI2_MOSI{slash}TIM1_CH3N-Pad28)") (class "Default")
      (node (ref "1U1") (pin "28") (pinfunction "PB15/SPI2_MOSI/TIM1_CH3N_28") (pintype "input"))
    )
    (net (code "79") (name "unconnected-(1U1-PC14-OSC32_IN-Pad3)") (class "Default")
      (node (ref "1U1") (pin "3") (pinfunction "PC14-OSC32_IN_3") (pintype "input"))
    )
    (net (code "80") (name "unconnected-(1U1-PC15-OSC32_OUT-Pad4)") (class "Default")
      (node (ref "1U1") (pin "4") (pinfunction "PC15-OSC32_OUT_4") (pintype "input"))
    )
    (net (code "81") (name "unconnected-(2U1-ENA-Pad5)") (class "Default")
      (node (ref "2U1") (pin "5") (pinfunction "ENA_5") (pintype "input"))
    )
    (net (code "82") (name "unconnected-(2U1-NC-Pad2)") (class "Default")
      (node (ref "2U1") (pin "2") (pinfunction "NC_2") (pintype "no_connect"))
    )
    (net (code "83") (name "unconnected-(2U1-NC-Pad3)") (class "Default")
      (node (ref "2U1") (pin "3") (pinfunction "NC_3") (pintype "no_connect"))
    )
    (net (code "84") (name "unconnected-(IMU-Pad5)") (class "Default")
      (node (ref "IMU") (pin "5") (pinfunction "5_5") (pintype "passive"))
    )
    (net (code "85") (name "unconnected-(RPI_UART-Pad3)") (class "Default")
      (node (ref "RPI_UART") (pin "3") (pinfunction "3_3") (pintype "passive"))
    )
    (net (code "86") (name "unconnected-(U$1-Pad2)") (class "Default")
      (node (ref "U$1") (pin "2") (pinfunction "2_2") (pintype "bidirectional"))
    )
    (net (code "87") (name "unconnected-(U$1-Pad3V3)") (class "Default")
      (node (ref "U$1") (pin "3V3") (pinfunction "3V3_3V3") (pintype "bidirectional"))
    )
    (net (code "88") (name "unconnected-(U$1-Pad3{slash}CANTX)") (class "Default")
      (node (ref "U$1") (pin "3/CANTX") (pinfunction "3/CANTX_3/CANTX") (pintype "bidirectional"))
    )
    (net (code "89") (name "unconnected-(U$1-Pad4{slash}CANRX)") (class "Default")
      (node (ref "U$1") (pin "4/CANRX") (pinfunction "4/CANRX_4/CANRX") (pintype "bidirectional"))
    )
    (net (code "90") (name "unconnected-(U$1-Pad5)") (class "Default")
      (node (ref "U$1") (pin "5") (pinfunction "5_5") (pintype "bidirectional"))
    )
    (net (code "91") (name "unconnected-(U$1-Pad6)") (class "Default")
      (node (ref "U$1") (pin "6") (pinfunction "6_6") (pintype "bidirectional"))
    )
    (net (code "92") (name "unconnected-(U$1-Pad11{slash}MOSI)") (class "Default")
      (node (ref "U$1") (pin "11/MOSI") (pinfunction "11/MOSI_11/MOSI") (pintype "bidirectional"))
    )
    (net (code "93") (name "unconnected-(U$1-Pad12{slash}MISO)") (class "Default")
      (node (ref "U$1") (pin "12/MISO") (pinfunction "12/MISO_12/MISO") (pintype "bidirectional"))
    )
    (net (code "94") (name "unconnected-(U$1-Pad16{slash}A2)") (class "Default")
      (node (ref "U$1") (pin "16/A2") (pinfunction "16/A2_16/A2") (pintype "bidirectional"))
    )
    (net (code "95") (name "unconnected-(U$1-Pad17{slash}A3)") (class "Default")
      (node (ref "U$1") (pin "17/A3") (pinfunction "17/A3_17/A3") (pintype "bidirectional"))
    )
    (net (code "96") (name "unconnected-(U$1-Pad18{slash}A4{slash}SDA)") (class "Default")
      (node (ref "U$1") (pin "18/A4/SDA") (pinfunction "18/A4/SDA_18/A4/SDA") (pintype "bidirectional"))
    )
    (net (code "97") (name "unconnected-(U$1-Pad19{slash}A5{slash}SCL)") (class "Default")
      (node (ref "U$1") (pin "19/A5/SCL") (pinfunction "19/A5/SCL_19/A5/SCL") (pintype "bidirectional"))
    )
    (net (code "98") (name "unconnected-(U$1-Pad20{slash}A6)") (class "Default")
      (node (ref "U$1") (pin "20/A6") (pinfunction "20/A6_20/A6") (pintype "bidirectional"))
    )
    (net (code "99") (name "unconnected-(U$1-Pad21{slash}A7)") (class "Default")
      (node (ref "U$1") (pin "21/A7") (pinfunction "21/A7_21/A7") (pintype "bidirectional"))
    )
    (net (code "100") (name "unconnected-(U$1-Pad22{slash}A8)") (class "Default")
      (node (ref "U$1") (pin "22/A8") (pinfunction "22/A8_22/A8") (pintype "bidirectional"))
    )
    (net (code "101") (name "unconnected-(U$1-Pad23{slash}A9)") (class "Default")
      (node (ref "U$1") (pin "23/A9") (pinfunction "23/A9_23/A9") (pintype "bidirectional"))
    )
    (net (code "102") (name "unconnected-(U$1-Pad28)") (class "Default")
      (node (ref "U$1") (pin "28") (pinfunction "28_28") (pintype "bidirectional"))
    )
    (net (code "103") (name "unconnected-(U$1-Pad29)") (class "Default")
      (node (ref "U$1") (pin "29") (pinfunction "29_29") (pintype "bidirectional"))
    )
    (net (code "104") (name "unconnected-(U$1-Pad30)") (class "Default")
      (node (ref "U$1") (pin "30") (pinfunction "30_30") (pintype "bidirectional"))
    )
    (net (code "105") (name "unconnected-(U$1-PadAGND)") (class "Default")
      (node (ref "U$1") (pin "AGND") (pinfunction "AGND_AGND") (pintype "bidirectional"))
    )
    (net (code "106") (name "unconnected-(U$1-PadGND2)") (class "Default")
      (node (ref "U$1") (pin "GND2") (pinfunction "GND2_GND2") (pintype "bidirectional"))
    )
    (net (code "107") (name "unconnected-(U$4-S-Pad3)") (class "Default")
      (node (ref "U$4") (pin "3") (pinfunction "S_3") (pintype "passive"))
    )
    (net (code "108") (name "unconnected-(U2-KEY-Pad6)") (class "Default")
      (node (ref "U2") (pin "6") (pinfunction "KEY_6") (pintype "bidirectional"))
    )
    (net (code "109") (name "unconnected-(U2-STATE-Pad1)") (class "Default")
      (node (ref "U2") (pin "1") (pinfunction "STATE_1") (pintype "bidirectional"))
    )
  )
)
